# sensor.net
KiCad netlist of a schematic drawn in Altium Designer
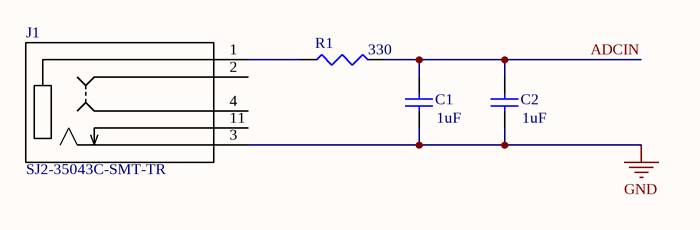
[diagram p0: sensor.SchDoc]

(export (version "E")
  (design (tool "Eeschema 10.0.6"))
  (components
    (comp (ref "C1")
      (value "1uF")
      (footprint "1608[0603]")
      (description "CAP CER 1UF 16V X7R 0603")
      (fields
        (field (name "DIGI-KEY PART NUMBER") "1276-6524-1-ND")
        (field (name "MANUFACTURER") "Samsung Electro-Mechanics")
        (field (name "PUBLISHER") "Altium Limited")
      )
      (libsource (lib "Miscellaneous Devices") (part "Cap"))
    )
    (comp (ref "C2")
      (value "1uF")
      (footprint "1608[0603]")
      (description "CAP CER 1UF 16V X7R 0603")
      (fields
        (field (name "DIGI-KEY PART NUMBER") "1276-6524-1-ND")
        (field (name "MANUFACTURER") "Samsung Electro-Mechanics")
        (field (name "PUBLISHER") "Altium Limited")
      )
      (libsource (lib "Miscellaneous Devices") (part "Cap"))
    )
    (comp (ref "J1")
      (value "SJ2-35043C-SMT-TR")
      (footprint "CUI_SJ2-35043C-SMT-TR")
      (description "AUDIO JACK, 3.5 MM, RT, 4 CONDUC")
      (fields
        (field (name "DIGI-KEY PART NUMBER") "CP-SJ2-35043C-SMT-CT-ND")
        (field (name "MANUFACTURER") "CUI Inc.")
      )
      (libsource (lib "SJ2-35043C-SMT-TR") (part "SJ2-35043C-SMT-TR"))
    )
    (comp (ref "R1")
      (value "330")
      (footprint "1608[0603]")
      (description "RES SMD 330 OHM 5% 1/10W 0603")
      (fields
        (field (name "DIGI-KEY PART NUMBER") "541-4060-1-ND")
        (field (name "MANUFACTURER") "Vishay Dale")
        (field (name "PUBLISHER") "Altium Limited")
      )
      (libsource (lib "Miscellaneous Devices") (part "Res3"))
    )
  )
  (nets
    (net (code "1") (name "/ADCIN") (class "Default")
      (node (ref "C1") (pin "2") (pinfunction "2_2") (pintype "passive"))
      (node (ref "C2") (pin "2") (pinfunction "2_2") (pintype "passive"))
      (node (ref "R1") (pin "2") (pinfunction "2_2") (pintype "passive"))
    )
    (net (code "2") (name "GND") (class "Default")
      (node (ref "C1") (pin "1") (pinfunction "1_1") (pintype "passive"))
      (node (ref "C2") (pin "1") (pinfunction "1_1") (pintype "passive"))
      (node (ref "J1") (pin "3") (pinfunction "RING_3") (pintype "passive"))
    )
    (net (code "3") (name "Net-(J1-SLEEVE)") (class "Default")
      (node (ref "J1") (pin "1") (pinfunction "SLEEVE_1") (pintype "passive"))
      (node (ref "R1") (pin "1") (pinfunction "1_1") (pintype "passive"))
    )
    (net (code "4") (name "unconnected-(J1-RING_SWITCH-Pad11)") (class "Default")
      (node (ref "J1") (pin "11") (pinfunction "RING_SWITCH_11") (pintype "passive"))
    )
    (net (code "5") (name "unconnected-(J1-TIP_1-Pad2)") (class "Default")
      (node (ref "J1") (pin "2") (pinfunction "TIP_1_2") (pintype "passive"))
    )
    (net (code "6") (name "unconnected-(J1-TIP_2-Pad4)") (class "Default")
      (node (ref "J1") (pin "4") (pinfunction "TIP_2_4") (pintype "passive"))
    )
  )
)
